# TUSB8041_Connectors_2.net
KiCad netlist of a schematic drawn in Altium Designer
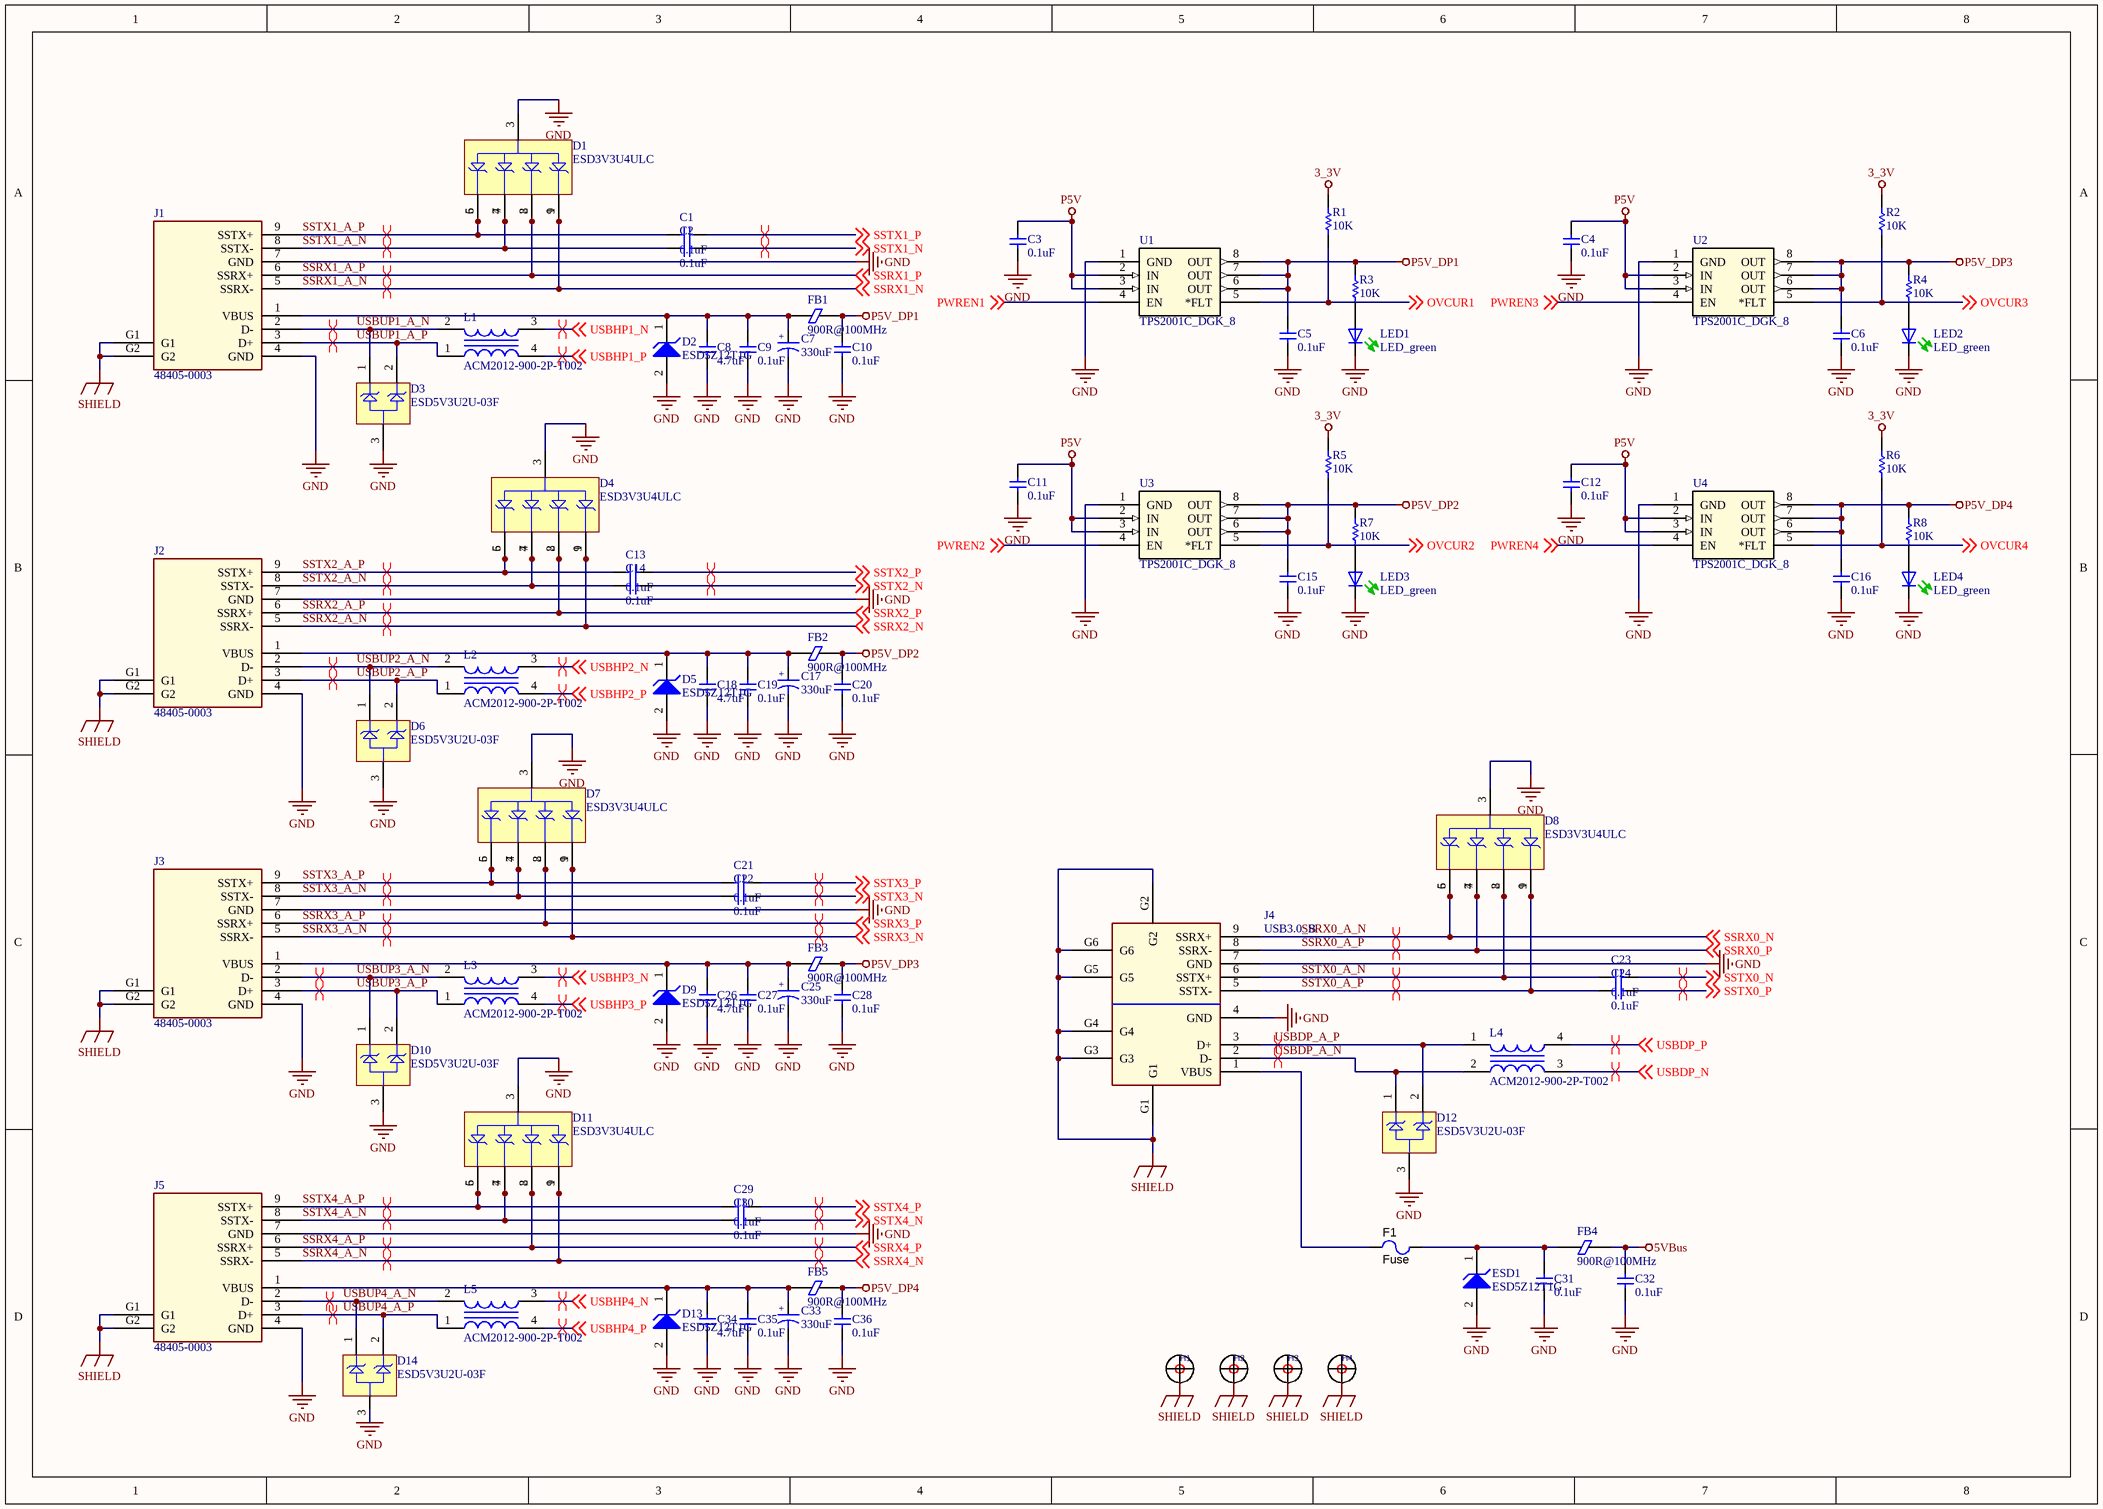
[diagram p0: TUSB8041_Connectors_2.SchDoc]

(export (version "E")
  (design (tool "Eeschema 10.0.6"))
  (components
    (comp (ref "C1")
      (value "0.1uF")
      (footprint "CAP0402")
      (description "Capacitor")
      (fields (field (name "PUBLISHER") "Altium Limited"))
      (libsource (lib "TUSB8041_USB_3.0_Hub") (part "CAP"))
    )
    (comp (ref "C2")
      (value "0.1uF")
      (footprint "CAP0402")
      (description "Capacitor")
      (fields (field (name "PUBLISHER") "Altium Limited"))
      (libsource (lib "TUSB8041_USB_3.0_Hub") (part "CAP"))
    )
    (comp (ref "C3")
      (value "0.1uF")
      (footprint "CAP0603")
      (description "Capacitor")
      (fields (field (name "PUBLISHER") "Altium Limited"))
      (libsource (lib "TUSB8041_USB_3.0_Hub") (part "CAP"))
    )
    (comp (ref "C4")
      (value "0.1uF")
      (footprint "CAP0603")
      (description "Capacitor")
      (fields (field (name "PUBLISHER") "Altium Limited"))
      (libsource (lib "TUSB8041_USB_3.0_Hub") (part "CAP"))
    )
    (comp (ref "C5")
      (value "0.1uF")
      (footprint "CAP0603")
      (description "Capacitor")
      (fields (field (name "PUBLISHER") "Altium Limited"))
      (libsource (lib "TUSB8041_USB_3.0_Hub") (part "CAP"))
    )
    (comp (ref "C6")
      (value "0.1uF")
      (footprint "CAP0603")
      (description "Capacitor")
      (fields (field (name "PUBLISHER") "Altium Limited"))
      (libsource (lib "TUSB8041_USB_3.0_Hub") (part "CAP"))
    )
    (comp (ref "C7")
      (value "330uF")
      (footprint "CAP7343_TANT")
      (libsource (lib "TUSB8041_USB_3.0_Hub") (part "CAP_POL"))
    )
    (comp (ref "C8")
      (value "4.7uF")
      (footprint "CAP0603")
      (description "Capacitor")
      (fields (field (name "PUBLISHER") "Altium Limited"))
      (libsource (lib "TUSB8041_USB_3.0_Hub") (part "CAP"))
    )
    (comp (ref "C9")
      (value "0.1uF")
      (footprint "CAP0603")
      (description "Capacitor")
      (fields (field (name "PUBLISHER") "Altium Limited"))
      (libsource (lib "TUSB8041_USB_3.0_Hub") (part "CAP"))
    )
    (comp (ref "C10")
      (value "0.1uF")
      (footprint "CAP0603")
      (description "Capacitor")
      (fields (field (name "PUBLISHER") "Altium Limited"))
      (libsource (lib "TUSB8041_USB_3.0_Hub") (part "CAP"))
    )
    (comp (ref "C11")
      (value "0.1uF")
      (footprint "CAP0603")
      (description "Capacitor")
      (fields (field (name "PUBLISHER") "Altium Limited"))
      (libsource (lib "TUSB8041_USB_3.0_Hub") (part "CAP"))
    )
    (comp (ref "C12")
      (value "0.1uF")
      (footprint "CAP0603")
      (description "Capacitor")
      (fields (field (name "PUBLISHER") "Altium Limited"))
      (libsource (lib "TUSB8041_USB_3.0_Hub") (part "CAP"))
    )
    (comp (ref "C13")
      (value "0.1uF")
      (footprint "CAP0402")
      (description "Capacitor")
      (fields (field (name "PUBLISHER") "Altium Limited"))
      (libsource (lib "TUSB8041_USB_3.0_Hub") (part "CAP"))
    )
    (comp (ref "C14")
      (value "0.1uF")
      (footprint "CAP0402")
      (description "Capacitor")
      (fields (field (name "PUBLISHER") "Altium Limited"))
      (libsource (lib "TUSB8041_USB_3.0_Hub") (part "CAP"))
    )
    (comp (ref "C15")
      (value "0.1uF")
      (footprint "CAP0603")
      (description "Capacitor")
      (fields (field (name "PUBLISHER") "Altium Limited"))
      (libsource (lib "TUSB8041_USB_3.0_Hub") (part "CAP"))
    )
    (comp (ref "C16")
      (value "0.1uF")
      (footprint "CAP0603")
      (description "Capacitor")
      (fields (field (name "PUBLISHER") "Altium Limited"))
      (libsource (lib "TUSB8041_USB_3.0_Hub") (part "CAP"))
    )
    (comp (ref "C17")
      (value "330uF")
      (footprint "CAP7343_TANT")
      (libsource (lib "TUSB8041_USB_3.0_Hub") (part "CAP_POL"))
    )
    (comp (ref "C18")
      (value "4.7uF")
      (footprint "CAP0603")
      (description "Capacitor")
      (fields (field (name "PUBLISHER") "Altium Limited"))
      (libsource (lib "TUSB8041_USB_3.0_Hub") (part "CAP"))
    )
    (comp (ref "C19")
      (value "0.1uF")
      (footprint "CAP0603")
      (description "Capacitor")
      (fields (field (name "PUBLISHER") "Altium Limited"))
      (libsource (lib "TUSB8041_USB_3.0_Hub") (part "CAP"))
    )
    (comp (ref "C20")
      (value "0.1uF")
      (footprint "CAP0603")
      (description "Capacitor")
      (fields (field (name "PUBLISHER") "Altium Limited"))
      (libsource (lib "TUSB8041_USB_3.0_Hub") (part "CAP"))
    )
    (comp (ref "C21")
      (value "0.1uF")
      (footprint "CAP0402")
      (description "Capacitor")
      (fields (field (name "PUBLISHER") "Altium Limited"))
      (libsource (lib "TUSB8041_USB_3.0_Hub") (part "CAP"))
    )
    (comp (ref "C22")
      (value "0.1uF")
      (footprint "CAP0402")
      (description "Capacitor")
      (fields (field (name "PUBLISHER") "Altium Limited"))
      (libsource (lib "TUSB8041_USB_3.0_Hub") (part "CAP"))
    )
    (comp (ref "C23")
      (value "0.1uF")
      (footprint "CAP0402")
      (description "Capacitor")
      (fields (field (name "PUBLISHER") "Altium Limited"))
      (libsource (lib "TUSB8041_USB_3.0_Hub") (part "CAP"))
    )
    (comp (ref "C24")
      (value "0.1uF")
      (footprint "CAP0402")
      (description "Capacitor")
      (fields (field (name "PUBLISHER") "Altium Limited"))
      (libsource (lib "TUSB8041_USB_3.0_Hub") (part "CAP"))
    )
    (comp (ref "C25")
      (value "330uF")
      (footprint "CAP7343_TANT")
      (libsource (lib "TUSB8041_USB_3.0_Hub") (part "CAP_POL"))
    )
    (comp (ref "C26")
      (value "4.7uF")
      (footprint "CAP0603")
      (description "Capacitor")
      (fields (field (name "PUBLISHER") "Altium Limited"))
      (libsource (lib "TUSB8041_USB_3.0_Hub") (part "CAP"))
    )
    (comp (ref "C27")
      (value "0.1uF")
      (footprint "CAP0603")
      (description "Capacitor")
      (fields (field (name "PUBLISHER") "Altium Limited"))
      (libsource (lib "TUSB8041_USB_3.0_Hub") (part "CAP"))
    )
    (comp (ref "C28")
      (value "0.1uF")
      (footprint "CAP0603")
      (description "Capacitor")
      (fields (field (name "PUBLISHER") "Altium Limited"))
      (libsource (lib "TUSB8041_USB_3.0_Hub") (part "CAP"))
    )
    (comp (ref "C29")
      (value "0.1uF")
      (footprint "CAP0402")
      (description "Capacitor")
      (fields (field (name "PUBLISHER") "Altium Limited"))
      (libsource (lib "TUSB8041_USB_3.0_Hub") (part "CAP"))
    )
    (comp (ref "C30")
      (value "0.1uF")
      (footprint "CAP0402")
      (description "Capacitor")
      (fields (field (name "PUBLISHER") "Altium Limited"))
      (libsource (lib "TUSB8041_USB_3.0_Hub") (part "CAP"))
    )
    (comp (ref "C31")
      (value "0.1uF")
      (footprint "CAP0603")
      (description "Capacitor")
      (fields (field (name "PUBLISHER") "Altium Limited"))
      (libsource (lib "TUSB8041_USB_3.0_Hub") (part "CAP"))
    )
    (comp (ref "C32")
      (value "0.1uF")
      (footprint "CAP0603")
      (description "Capacitor")
      (fields (field (name "PUBLISHER") "Altium Limited"))
      (libsource (lib "TUSB8041_USB_3.0_Hub") (part "CAP"))
    )
    (comp (ref "C33")
      (value "330uF")
      (footprint "CAP7343_TANT")
      (libsource (lib "TUSB8041_USB_3.0_Hub") (part "CAP_POL"))
    )
    (comp (ref "C34")
      (value "4.7uF")
      (footprint "CAP0603")
      (description "Capacitor")
      (fields (field (name "PUBLISHER") "Altium Limited"))
      (libsource (lib "TUSB8041_USB_3.0_Hub") (part "CAP"))
    )
    (comp (ref "C35")
      (value "0.1uF")
      (footprint "CAP0603")
      (description "Capacitor")
      (fields (field (name "PUBLISHER") "Altium Limited"))
      (libsource (lib "TUSB8041_USB_3.0_Hub") (part "CAP"))
    )
    (comp (ref "C36")
      (value "0.1uF")
      (footprint "CAP0603")
      (description "Capacitor")
      (fields (field (name "PUBLISHER") "Altium Limited"))
      (libsource (lib "TUSB8041_USB_3.0_Hub") (part "CAP"))
    )
    (comp (ref "D1")
      (value "ESD3V3U4ULC")
      (footprint "PG-TSLP-9-1")
      (description "Ultra-Low Capacitance ESD / Transient Protection Array, -40 to 125 degC, PG-TSLP-9-1, Reel, Green")
      (fields (field (name "MANUFACTURER") "Infineon"))
      (libsource (lib "小车") (part "ESD3V3U4ULC"))
    )
    (comp (ref "D2")
      (value "ESD5Z12T1G")
      (footprint "ONSC-SOD-523-2-502-01_V")
      (fields (field (name "MANUFACTURER") "On Semiconductor"))
      (libsource (lib "Altium Content Vault") (part "ONSC-K1A2-2"))
    )
    (comp (ref "D3")
      (value "ESD5V3U2U-03F")
      (footprint "INF-PG-TSFP-3-1_V")
      (description "Ultra-Low Capacitance ESD Diode Array, -40 to 125 degC, PG-TSFP-3-1, Reel, Green")
      (fields (field (name "MANUFACTURER") "Infineon"))
      (libsource (lib "Altium Content Vault") (part "INF-D_K1K2A3-3-A"))
    )
    (comp (ref "D4")
      (value "ESD3V3U4ULC")
      (footprint "PG-TSLP-9-1")
      (description "Ultra-Low Capacitance ESD / Transient Protection Array, -40 to 125 degC, PG-TSLP-9-1, Reel, Green")
      (fields (field (name "MANUFACTURER") "Infineon"))
      (libsource (lib "小车") (part "ESD3V3U4ULC"))
    )
    (comp (ref "D5")
      (value "ESD5Z12T1G")
      (footprint "ONSC-SOD-523-2-502-01_V")
      (fields (field (name "MANUFACTURER") "On Semiconductor"))
      (libsource (lib "Altium Content Vault") (part "ONSC-K1A2-2"))
    )
    (comp (ref "D6")
      (value "ESD5V3U2U-03F")
      (footprint "INF-PG-TSFP-3-1_V")
      (description "Ultra-Low Capacitance ESD Diode Array, -40 to 125 degC, PG-TSFP-3-1, Reel, Green")
      (fields (field (name "MANUFACTURER") "Infineon"))
      (libsource (lib "Altium Content Vault") (part "INF-D_K1K2A3-3-A"))
    )
    (comp (ref "D7")
      (value "ESD3V3U4ULC")
      (footprint "PG-TSLP-9-1")
      (description "Ultra-Low Capacitance ESD / Transient Protection Array, -40 to 125 degC, PG-TSLP-9-1, Reel, Green")
      (fields (field (name "MANUFACTURER") "Infineon"))
      (libsource (lib "小车") (part "ESD3V3U4ULC"))
    )
    (comp (ref "D8")
      (value "ESD3V3U4ULC")
      (footprint "PG-TSLP-9-1")
      (description "Ultra-Low Capacitance ESD / Transient Protection Array, -40 to 125 degC, PG-TSLP-9-1, Reel, Green")
      (fields (field (name "MANUFACTURER") "Infineon"))
      (libsource (lib "小车") (part "ESD3V3U4ULC"))
    )
    (comp (ref "D9")
      (value "ESD5Z12T1G")
      (footprint "ONSC-SOD-523-2-502-01_V")
      (fields (field (name "MANUFACTURER") "On Semiconductor"))
      (libsource (lib "Altium Content Vault") (part "ONSC-K1A2-2"))
    )
    (comp (ref "D10")
      (value "ESD5V3U2U-03F")
      (footprint "INF-PG-TSFP-3-1_V")
      (description "Ultra-Low Capacitance ESD Diode Array, -40 to 125 degC, PG-TSFP-3-1, Reel, Green")
      (fields (field (name "MANUFACTURER") "Infineon"))
      (libsource (lib "Altium Content Vault") (part "INF-D_K1K2A3-3-A"))
    )
    (comp (ref "D11")
      (value "ESD3V3U4ULC")
      (footprint "PG-TSLP-9-1")
      (description "Ultra-Low Capacitance ESD / Transient Protection Array, -40 to 125 degC, PG-TSLP-9-1, Reel, Green")
      (fields (field (name "MANUFACTURER") "Infineon"))
      (libsource (lib "小车") (part "ESD3V3U4ULC"))
    )
    (comp (ref "D12")
      (value "ESD5V3U2U-03F")
      (footprint "INF-PG-TSFP-3-1_V")
      (description "Ultra-Low Capacitance ESD Diode Array, -40 to 125 degC, PG-TSFP-3-1, Reel, Green")
      (fields (field (name "MANUFACTURER") "Infineon"))
      (libsource (lib "Altium Content Vault") (part "INF-D_K1K2A3-3-A"))
    )
    (comp (ref "D13")
      (value "ESD5Z12T1G")
      (footprint "ONSC-SOD-523-2-502-01_V")
      (fields (field (name "MANUFACTURER") "On Semiconductor"))
      (libsource (lib "Altium Content Vault") (part "ONSC-K1A2-2"))
    )
    (comp (ref "D14")
      (value "ESD5V3U2U-03F")
      (footprint "INF-PG-TSFP-3-1_V")
      (description "Ultra-Low Capacitance ESD Diode Array, -40 to 125 degC, PG-TSFP-3-1, Reel, Green")
      (fields (field (name "MANUFACTURER") "Infineon"))
      (libsource (lib "Altium Content Vault") (part "INF-D_K1K2A3-3-A"))
    )
    (comp (ref "ESD1")
      (value "ESD5Z12T1G")
      (footprint "ONSC-SOD-523-2-502-01_V")
      (fields (field (name "MANUFACTURER") "On Semiconductor"))
      (libsource (lib "Altium Content Vault") (part "ONSC-K1A2-2"))
    )
    (comp (ref "F1")
      (value "Fuse")
      (footprint "FUSE1206")
      (fields
        (field (name "PARTNUMBER") "NANOSMDC020F-2")
        (field (name "MANUFACTURER") "TE Connectivity")
        (field (name "PUBLISHER") "Texas Instruments")
        (field (name "SYMBOLCREATOR") "a0412235")
      )
      (libsource (lib "TUSB8041_USB_3.0_Hub") (part "Fuse"))
    )
    (comp (ref "FB1")
      (value "900R@100MHz")
      (footprint "L0805")
      (libsource (lib "TUSB8041_USB_3.0_Hub") (part "Ferrite Bead"))
    )
    (comp (ref "FB2")
      (value "900R@100MHz")
      (footprint "L0805")
      (libsource (lib "TUSB8041_USB_3.0_Hub") (part "Ferrite Bead"))
    )
    (comp (ref "FB3")
      (value "900R@100MHz")
      (footprint "L0805")
      (libsource (lib "TUSB8041_USB_3.0_Hub") (part "Ferrite Bead"))
    )
    (comp (ref "FB4")
      (value "900R@100MHz")
      (footprint "L0805")
      (libsource (lib "TUSB8041_USB_3.0_Hub") (part "Ferrite Bead"))
    )
    (comp (ref "FB5")
      (value "900R@100MHz")
      (footprint "L0805")
      (libsource (lib "TUSB8041_USB_3.0_Hub") (part "Ferrite Bead"))
    )
    (comp (ref "H1")
      (value "HOLE")
      (footprint "HOLE_Φ3_1_2D")
      (libsource (lib "TUSB8041_USB_3.0_Hub") (part "HOLE"))
    )
    (comp (ref "H2")
      (value "HOLE")
      (footprint "HOLE_Φ3_1_2D")
      (libsource (lib "TUSB8041_USB_3.0_Hub") (part "HOLE"))
    )
    (comp (ref "H3")
      (value "HOLE")
      (footprint "HOLE_Φ3_1_2D")
      (libsource (lib "TUSB8041_USB_3.0_Hub") (part "HOLE"))
    )
    (comp (ref "H4")
      (value "HOLE")
      (footprint "HOLE_Φ3_1_2D")
      (libsource (lib "TUSB8041_USB_3.0_Hub") (part "HOLE"))
    )
    (comp (ref "J1")
      (value "48405-0003")
      (footprint "CN_USB30_A")
      (libsource (lib "TUSB8041_USB_3.0_Hub") (part "USB-UEA11123-4HK1-4H"))
    )
    (comp (ref "J2")
      (value "48405-0003")
      (footprint "CN_USB30_A")
      (libsource (lib "TUSB8041_USB_3.0_Hub") (part "USB-UEA11123-4HK1-4H"))
    )
    (comp (ref "J3")
      (value "48405-0003")
      (footprint "CN_USB30_A")
      (libsource (lib "TUSB8041_USB_3.0_Hub") (part "USB-UEA11123-4HK1-4H"))
    )
    (comp (ref "J4")
      (value "USB3.0_B")
      (footprint "ASS_4224_CO")
      (libsource (lib "TUSB8041_USB_3.0_Hub") (part "USB3.0_B"))
    )
    (comp (ref "J5")
      (value "48405-0003")
      (footprint "CN_USB30_A")
      (libsource (lib "TUSB8041_USB_3.0_Hub") (part "USB-UEA11123-4HK1-4H"))
    )
    (comp (ref "L1")
      (value "ACM2012-900-2P-T002")
      (footprint "TDK-ACM2012_V")
      (description "Common Mode Filter, 90 Ohm, 50 V, -40 to 85 degC, 4-Pin SMD, RoHS, Tape and Reel")
      (fields (field (name "PART NO") "ACM2012-900-2P-T") (field (name "MANUFACTURER") "TDKCorporation"))
      (libsource (lib "") (part "IND-CHOKE-4_C_1"))
    )
    (comp (ref "L2")
      (value "ACM2012-900-2P-T002")
      (footprint "TDK-ACM2012_V")
      (description "Common Mode Filter, 90 Ohm, 50 V, -40 to 85 degC, 4-Pin SMD, RoHS, Tape and Reel")
      (fields (field (name "PART NO") "ACM2012-900-2P-T") (field (name "MANUFACTURER") "TDKCorporation"))
      (libsource (lib "") (part "IND-CHOKE-4_C_1"))
    )
    (comp (ref "L3")
      (value "ACM2012-900-2P-T002")
      (footprint "TDK-ACM2012_V")
      (description "Common Mode Filter, 90 Ohm, 50 V, -40 to 85 degC, 4-Pin SMD, RoHS, Tape and Reel")
      (fields (field (name "PART NO") "ACM2012-900-2P-T") (field (name "MANUFACTURER") "TDKCorporation"))
      (libsource (lib "") (part "IND-CHOKE-4_C_1"))
    )
    (comp (ref "L4")
      (value "ACM2012-900-2P-T002")
      (footprint "TDK-ACM2012_V")
      (description "Common Mode Filter, 90 Ohm, 50 V, -40 to 85 degC, 4-Pin SMD, RoHS, Tape and Reel")
      (fields (field (name "PART NO") "ACM2012-900-2P-T") (field (name "MANUFACTURER") "TDKCorporation"))
      (libsource (lib "Altium Content Vault") (part "IND-CHOKE-4_C"))
    )
    (comp (ref "L5")
      (value "ACM2012-900-2P-T002")
      (footprint "TDK-ACM2012_V")
      (description "Common Mode Filter, 90 Ohm, 50 V, -40 to 85 degC, 4-Pin SMD, RoHS, Tape and Reel")
      (fields (field (name "PART NO") "ACM2012-900-2P-T") (field (name "MANUFACTURER") "TDKCorporation"))
      (libsource (lib "") (part "IND-CHOKE-4_C_1"))
    )
    (comp (ref "LED1")
      (value "LED_green")
      (footprint "LED-0603-GREEN")
      (libsource (lib "TUSB8041_USB_3.0_Hub") (part "LED_green"))
    )
    (comp (ref "LED2")
      (value "LED_green")
      (footprint "LED-0603-GREEN")
      (libsource (lib "TUSB8041_USB_3.0_Hub") (part "LED_green"))
    )
    (comp (ref "LED3")
      (value "LED_green")
      (footprint "LED-0603-GREEN")
      (libsource (lib "TUSB8041_USB_3.0_Hub") (part "LED_green"))
    )
    (comp (ref "LED4")
      (value "LED_green")
      (footprint "LED-0603-GREEN")
      (libsource (lib "TUSB8041_USB_3.0_Hub") (part "LED_green"))
    )
    (comp (ref "R1")
      (value "10K")
      (footprint "RES0603")
      (description "Resistor")
      (fields (field (name "PUBLISHER") "Altium Limited"))
      (libsource (lib "TUSB8041_USB_3.0_Hub") (part "RES"))
    )
    (comp (ref "R2")
      (value "10K")
      (footprint "RES0603")
      (description "Resistor")
      (fields (field (name "PUBLISHER") "Altium Limited"))
      (libsource (lib "TUSB8041_USB_3.0_Hub") (part "RES"))
    )
    (comp (ref "R3")
      (value "10K")
      (footprint "RES0603")
      (description "Resistor")
      (fields (field (name "PUBLISHER") "Altium Limited"))
      (libsource (lib "TUSB8041_USB_3.0_Hub") (part "RES"))
    )
    (comp (ref "R4")
      (value "10K")
      (footprint "RES0603")
      (description "Resistor")
      (fields (field (name "PUBLISHER") "Altium Limited"))
      (libsource (lib "TUSB8041_USB_3.0_Hub") (part "RES"))
    )
    (comp (ref "R5")
      (value "10K")
      (footprint "RES0603")
      (description "Resistor")
      (fields (field (name "PUBLISHER") "Altium Limited"))
      (libsource (lib "TUSB8041_USB_3.0_Hub") (part "RES"))
    )
    (comp (ref "R6")
      (value "10K")
      (footprint "RES0603")
      (description "Resistor")
      (fields (field (name "PUBLISHER") "Altium Limited"))
      (libsource (lib "TUSB8041_USB_3.0_Hub") (part "RES"))
    )
    (comp (ref "R7")
      (value "10K")
      (footprint "RES0603")
      (description "Resistor")
      (fields (field (name "PUBLISHER") "Altium Limited"))
      (libsource (lib "TUSB8041_USB_3.0_Hub") (part "RES"))
    )
    (comp (ref "R8")
      (value "10K")
      (footprint "RES0603")
      (description "Resistor")
      (fields (field (name "PUBLISHER") "Altium Limited"))
      (libsource (lib "TUSB8041_USB_3.0_Hub") (part "RES"))
    )
    (comp (ref "U1")
      (value "TPS2001C_DGK_8")
      (footprint "VSSOP8")
      (description "2A_MOS_PSW")
      (fields
        (field (name "MANUFACTURER_PART_NUMBER") "tps2001c_dgk_8")
        (field (name "GENERIC_PART_NUMBER") "TPS2001C")
      )
      (libsource (lib "TUSB8041_USB_3.0_Hub") (part "TPS2001C_DGK_8"))
    )
    (comp (ref "U2")
      (value "TPS2001C_DGK_8")
      (footprint "VSSOP8")
      (description "2A_MOS_PSW")
      (fields
        (field (name "MANUFACTURER_PART_NUMBER") "tps2001c_dgk_8")
        (field (name "GENERIC_PART_NUMBER") "TPS2001C")
      )
      (libsource (lib "TUSB8041_USB_3.0_Hub") (part "TPS2001C_DGK_8"))
    )
    (comp (ref "U3")
      (value "TPS2001C_DGK_8")
      (footprint "VSSOP8")
      (description "2A_MOS_PSW")
      (fields
        (field (name "MANUFACTURER_PART_NUMBER") "tps2001c_dgk_8")
        (field (name "GENERIC_PART_NUMBER") "TPS2001C")
      )
      (libsource (lib "TUSB8041_USB_3.0_Hub") (part "TPS2001C_DGK_8"))
    )
    (comp (ref "U4")
      (value "TPS2001C_DGK_8")
      (footprint "VSSOP8")
      (description "2A_MOS_PSW")
      (fields
        (field (name "MANUFACTURER_PART_NUMBER") "tps2001c_dgk_8")
        (field (name "GENERIC_PART_NUMBER") "TPS2001C")
      )
      (libsource (lib "TUSB8041_USB_3.0_Hub") (part "TPS2001C_DGK_8"))
    )
  )
  (nets
    (net (code "1") (name "/SSTX0_A_N") (class "Default")
      (node (ref "C23") (pin "2") (pinfunction "2_2") (pintype "passive"))
      (node (ref "D8") (pin "2") (pinfunction "K2_2") (pintype "passive"))
      (node (ref "D8") (pin "8") (pinfunction "K8_8") (pintype "passive"))
      (node (ref "J4") (pin "6") (pinfunction "SSTX+_6") (pintype "passive"))
    )
    (net (code "2") (name "/SSTX0_A_P") (class "Default")
      (node (ref "C24") (pin "2") (pinfunction "2_2") (pintype "passive"))
      (node (ref "D8") (pin "1") (pinfunction "K1_1") (pintype "passive"))
      (node (ref "D8") (pin "9") (pinfunction "K9_9") (pintype "passive"))
      (node (ref "J4") (pin "5") (pinfunction "SSTX-_5") (pintype "passive"))
    )
    (net (code "3") (name "/SSTX1_A_N") (class "Default")
      (node (ref "C2") (pin "2") (pinfunction "2_2") (pintype "passive"))
      (node (ref "D1") (pin "4") (pinfunction "K4_4") (pintype "passive"))
      (node (ref "D1") (pin "7") (pinfunction "K7_7") (pintype "passive"))
      (node (ref "J1") (pin "8") (pinfunction "SSTX-_8") (pintype "passive"))
    )
    (net (code "4") (name "/SSTX1_A_P") (class "Default")
      (node (ref "C1") (pin "2") (pinfunction "2_2") (pintype "passive"))
      (node (ref "D1") (pin "5") (pinfunction "K5_5") (pintype "passive"))
      (node (ref "D1") (pin "6") (pinfunction "K6_6") (pintype "passive"))
      (node (ref "J1") (pin "9") (pinfunction "SSTX+_9") (pintype "passive"))
    )
    (net (code "5") (name "/SSTX2_A_N") (class "Default")
      (node (ref "C14") (pin "2") (pinfunction "2_2") (pintype "passive"))
      (node (ref "D4") (pin "4") (pinfunction "K4_4") (pintype "passive"))
      (node (ref "D4") (pin "7") (pinfunction "K7_7") (pintype "passive"))
      (node (ref "J2") (pin "8") (pinfunction "SSTX-_8") (pintype "passive"))
    )
    (net (code "6") (name "/SSTX2_A_P") (class "Default")
      (node (ref "C13") (pin "2") (pinfunction "2_2") (pintype "passive"))
      (node (ref "D4") (pin "5") (pinfunction "K5_5") (pintype "passive"))
      (node (ref "D4") (pin "6") (pinfunction "K6_6") (pintype "passive"))
      (node (ref "J2") (pin "9") (pinfunction "SSTX+_9") (pintype "passive"))
    )
    (net (code "7") (name "/SSTX3_A_N") (class "Default")
      (node (ref "C22") (pin "2") (pinfunction "2_2") (pintype "passive"))
      (node (ref "D7") (pin "4") (pinfunction "K4_4") (pintype "passive"))
      (node (ref "D7") (pin "7") (pinfunction "K7_7") (pintype "passive"))
      (node (ref "J3") (pin "8") (pinfunction "SSTX-_8") (pintype "passive"))
    )
    (net (code "8") (name "/SSTX3_A_P") (class "Default")
      (node (ref "C21") (pin "2") (pinfunction "2_2") (pintype "passive"))
      (node (ref "D7") (pin "5") (pinfunction "K5_5") (pintype "passive"))
      (node (ref "D7") (pin "6") (pinfunction "K6_6") (pintype "passive"))
      (node (ref "J3") (pin "9") (pinfunction "SSTX+_9") (pintype "passive"))
    )
    (net (code "9") (name "/SSTX4_A_N") (class "Default")
      (node (ref "C30") (pin "2") (pinfunction "2_2") (pintype "passive"))
      (node (ref "D11") (pin "4") (pinfunction "K4_4") (pintype "passive"))
      (node (ref "D11") (pin "7") (pinfunction "K7_7") (pintype "passive"))
      (node (ref "J5") (pin "8") (pinfunction "SSTX-_8") (pintype "passive"))
    )
    (net (code "10") (name "/SSTX4_A_P") (class "Default")
      (node (ref "C29") (pin "2") (pinfunction "2_2") (pintype "passive"))
      (node (ref "D11") (pin "5") (pinfunction "K5_5") (pintype "passive"))
      (node (ref "D11") (pin "6") (pinfunction "K6_6") (pintype "passive"))
      (node (ref "J5") (pin "9") (pinfunction "SSTX+_9") (pintype "passive"))
    )
    (net (code "11") (name "/USBDP_A_N") (class "Default")
      (node (ref "D12") (pin "1") (pinfunction "K1_1") (pintype "passive"))
      (node (ref "J4") (pin "2") (pinfunction "D-_2") (pintype "passive"))
      (node (ref "L4") (pin "2") (pinfunction "2_2") (pintype "passive"))
    )
    (net (code "12") (name "/USBDP_A_P") (class "Default")
      (node (ref "D12") (pin "2") (pinfunction "K2_2") (pintype "passive"))
      (node (ref "J4") (pin "3") (pinfunction "D+_3") (pintype "passive"))
      (node (ref "L4") (pin "1") (pinfunction "1_1") (pintype "passive"))
    )
    (net (code "13") (name "/USBUP1_A_N") (class "Default")
      (node (ref "D3") (pin "1") (pinfunction "K1_1") (pintype "passive"))
      (node (ref "J1") (pin "2") (pinfunction "D-_2") (pintype "passive"))
      (node (ref "L1") (pin "2") (pinfunction "2_2") (pintype "passive"))
    )
    (net (code "14") (name "/USBUP1_A_P") (class "Default")
      (node (ref "D3") (pin "2") (pinfunction "K2_2") (pintype "passive"))
      (node (ref "J1") (pin "3") (pinfunction "D+_3") (pintype "passive"))
      (node (ref "L1") (pin "1") (pinfunction "1_1") (pintype "passive"))
    )
    (net (code "15") (name "/USBUP2_A_N") (class "Default")
      (node (ref "D6") (pin "1") (pinfunction "K1_1") (pintype "passive"))
      (node (ref "J2") (pin "2") (pinfunction "D-_2") (pintype "passive"))
      (node (ref "L2") (pin "2") (pinfunction "2_2") (pintype "passive"))
    )
    (net (code "16") (name "/USBUP2_A_P") (class "Default")
      (node (ref "D6") (pin "2") (pinfunction "K2_2") (pintype "passive"))
      (node (ref "J2") (pin "3") (pinfunction "D+_3") (pintype "passive"))
      (node (ref "L2") (pin "1") (pinfunction "1_1") (pintype "passive"))
    )
    (net (code "17") (name "/USBUP3_A_N") (class "Default")
      (node (ref "D10") (pin "1") (pinfunction "K1_1") (pintype "passive"))
      (node (ref "J3") (pin "2") (pinfunction "D-_2") (pintype "passive"))
      (node (ref "L3") (pin "2") (pinfunction "2_2") (pintype "passive"))
    )
    (net (code "18") (name "/USBUP3_A_P") (class "Default")
      (node (ref "D10") (pin "2") (pinfunction "K2_2") (pintype "passive"))
      (node (ref "J3") (pin "3") (pinfunction "D+_3") (pintype "passive"))
      (node (ref "L3") (pin "1") (pinfunction "1_1") (pintype "passive"))
    )
    (net (code "19") (name "/USBUP4_A_N") (class "Default")
      (node (ref "D14") (pin "1") (pinfunction "K1_1") (pintype "passive"))
      (node (ref "J5") (pin "2") (pinfunction "D-_2") (pintype "passive"))
      (node (ref "L5") (pin "2") (pinfunction "2_2") (pintype "passive"))
    )
    (net (code "20") (name "/USBUP4_A_P") (class "Default")
      (node (ref "D14") (pin "2") (pinfunction "K2_2") (pintype "passive"))
      (node (ref "J5") (pin "3") (pinfunction "D+_3") (pintype "passive"))
      (node (ref "L5") (pin "1") (pinfunction "1_1") (pintype "passive"))
    )
    (net (code "21") (name "3_3V") (class "Default")
      (node (ref "R1") (pin "1") (pinfunction "1_1") (pintype "passive"))
      (node (ref "R2") (pin "1") (pinfunction "1_1") (pintype "passive"))
      (node (ref "R5") (pin "1") (pinfunction "1_1") (pintype "passive"))
      (node (ref "R6") (pin "1") (pinfunction "1_1") (pintype "passive"))
    )
    (net (code "22") (name "5VBus") (class "Default")
      (node (ref "C32") (pin "2") (pinfunction "2_2") (pintype "passive"))
      (node (ref "FB4") (pin "2") (pintype "passive"))
    )
    (net (code "23") (name "GND") (class "Default")
      (node (ref "C10") (pin "1") (pinfunction "1_1") (pintype "passive"))
      (node (ref "C11") (pin "1") (pinfunction "1_1") (pintype "passive"))
      (node (ref "C12") (pin "1") (pinfunction "1_1") (pintype "passive"))
      (node (ref "C15") (pin "1") (pinfunction "1_1") (pintype "passive"))
      (node (ref "C16") (pin "1") (pinfunction "1_1") (pintype "passive"))
      (node (ref "C17") (pin "2") (pinfunction "2_2") (pintype "passive"))
      (node (ref "C18") (pin "1") (pinfunction "1_1") (pintype "passive"))
      (node (ref "C19") (pin "1") (pinfunction "1_1") (pintype "passive"))
      (node (ref "C20") (pin "1") (pinfunction "1_1") (pintype "passive"))
      (node (ref "C25") (pin "2") (pinfunction "2_2") (pintype "passive"))
      (node (ref "C26") (pin "1") (pinfunction "1_1") (pintype "passive"))
      (node (ref "C27") (pin "1") (pinfunction "1_1") (pintype "passive"))
      (node (ref "C28") (pin "1") (pinfunction "1_1") (pintype "passive"))
      (node (ref "C3") (pin "1") (pinfunction "1_1") (pintype "passive"))
      (node (ref "C31") (pin "1") (pinfunction "1_1") (pintype "passive"))
      (node (ref "C32") (pin "1") (pinfunction "1_1") (pintype "passive"))
      (node (ref "C33") (pin "2") (pinfunction "2_2") (pintype "passive"))
      (node (ref "C34") (pin "1") (pinfunction "1_1") (pintype "passive"))
      (node (ref "C35") (pin "1") (pinfunction "1_1") (pintype "passive"))
      (node (ref "C36") (pin "1") (pinfunction "1_1") (pintype "passive"))
      (node (ref "C4") (pin "1") (pinfunction "1_1") (pintype "passive"))
      (node (ref "C5") (pin "1") (pinfunction "1_1") (pintype "passive"))
      (node (ref "C6") (pin "1") (pinfunction "1_1") (pintype "passive"))
      (node (ref "C7") (pin "2") (pinfunction "2_2") (pintype "passive"))
      (node (ref "C8") (pin "1") (pinfunction "1_1") (pintype "passive"))
      (node (ref "C9") (pin "1") (pinfunction "1_1") (pintype "passive"))
      (node (ref "D1") (pin "3") (pinfunction "A_3") (pintype "passive"))
      (node (ref "D10") (pin "3") (pinfunction "A_3") (pintype "passive"))
      (node (ref "D11") (pin "3") (pinfunction "A_3") (pintype "passive"))
      (node (ref "D12") (pin "3") (pinfunction "A_3") (pintype "passive"))
      (node (ref "D13") (pin "2") (pinfunction "A_2") (pintype "passive"))
      (node (ref "D14") (pin "3") (pinfunction "A_3") (pintype "passive"))
      (node (ref "D2") (pin "2") (pinfunction "A_2") (pintype "passive"))
      (node (ref "D3") (pin "3") (pinfunction "A_3") (pintype "passive"))
      (node (ref "D4") (pin "3") (pinfunction "A_3") (pintype "passive"))
      (node (ref "D5") (pin "2") (pinfunction "A_2") (pintype "passive"))
      (node (ref "D6") (pin "3") (pinfunction "A_3") (pintype "passive"))
      (node (ref "D7") (pin "3") (pinfunction "A_3") (pintype "passive"))
      (node (ref "D8") (pin "3") (pinfunction "A_3") (pintype "passive"))
      (node (ref "D9") (pin "2") (pinfunction "A_2") (pintype "passive"))
      (node (ref "ESD1") (pin "2") (pinfunction "A_2") (pintype "passive"))
      (node (ref "J1") (pin "4") (pinfunction "GND_4") (pintype "power_in"))
      (node (ref "J1") (pin "7") (pinfunction "GND_7") (pintype "power_in"))
      (node (ref "J2") (pin "4") (pinfunction "GND_4") (pintype "power_in"))
      (node (ref "J2") (pin "7") (pinfunction "GND_7") (pintype "power_in"))
      (node (ref "J3") (pin "4") (pinfunction "GND_4") (pintype "power_in"))
      (node (ref "J3") (pin "7") (pinfunction "GND_7") (pintype "power_in"))
      (node (ref "J4") (pin "4") (pinfunction "GND_4") (pintype "power_in"))
      (node (ref "J4") (pin "7") (pinfunction "GND_7") (pintype "power_in"))
      (node (ref "J5") (pin "4") (pinfunction "GND_4") (pintype "power_in"))
      (node (ref "J5") (pin "7") (pinfunction "GND_7") (pintype "power_in"))
      (node (ref "LED1") (pin "K") (pinfunction "C_K") (pintype "power_in"))
      (node (ref "LED2") (pin "K") (pinfunction "C_K") (pintype "power_in"))
      (node (ref "LED3") (pin "K") (pinfunction "C_K") (pintype "power_in"))
      (node (ref "LED4") (pin "K") (pinfunction "C_K") (pintype "power_in"))
      (node (ref "U1") (pin "1") (pinfunction "GND_1") (pintype "power_in"))
      (node (ref "U2") (pin "1") (pinfunction "GND_1") (pintype "power_in"))
      (node (ref "U3") (pin "1") (pinfunction "GND_1") (pintype "power_in"))
      (node (ref "U4") (pin "1") (pinfunction "GND_1") (pintype "power_in"))
    )
    (net (code "24") (name "Net-(D2-K)") (class "Default")
      (node (ref "C7") (pin "1") (pinfunction "1_1") (pintype "passive"))
      (node (ref "C8") (pin "2") (pinfunction "2_2") (pintype "passive"))
      (node (ref "C9") (pin "2") (pinfunction "2_2") (pintype "passive"))
      (node (ref "D2") (pin "1") (pinfunction "K_1") (pintype "passive"))
      (node (ref "FB1") (pin "1") (pintype "passive"))
      (node (ref "J1") (pin "1") (pinfunction "VBUS_1") (pintype "passive"))
    )
    (net (code "25") (name "Net-(D5-K)") (class "Default")
      (node (ref "C17") (pin "1") (pinfunction "1_1") (pintype "passive"))
      (node (ref "C18") (pin "2") (pinfunction "2_2") (pintype "passive"))
      (node (ref "C19") (pin "2") (pinfunction "2_2") (pintype "passive"))
      (node (ref "D5") (pin "1") (pinfunction "K_1") (pintype "passive"))
      (node (ref "FB2") (pin "1") (pintype "passive"))
      (node (ref "J2") (pin "1") (pinfunction "VBUS_1") (pintype "passive"))
    )
    (net (code "26") (name "Net-(D9-K)") (class "Default")
      (node (ref "C25") (pin "1") (pinfunction "1_1") (pintype "passive"))
      (node (ref "C26") (pin "2") (pinfunction "2_2") (pintype "passive"))
      (node (ref "C27") (pin "2") (pinfunction "2_2") (pintype "passive"))
      (node (ref "D9") (pin "1") (pinfunction "K_1") (pintype "passive"))
      (node (ref "FB3") (pin "1") (pintype "passive"))
      (node (ref "J3") (pin "1") (pinfunction "VBUS_1") (pintype "passive"))
    )
    (net (code "27") (name "Net-(D13-K)") (class "Default")
      (node (ref "C33") (pin "1") (pinfunction "1_1") (pintype "passive"))
      (node (ref "C34") (pin "2") (pinfunction "2_2") (pintype "passive"))
      (node (ref "C35") (pin "2") (pinfunction "2_2") (pintype "passive"))
      (node (ref "D13") (pin "1") (pinfunction "K_1") (pintype "passive"))
      (node (ref "FB5") (pin "1") (pintype "passive"))
      (node (ref "J5") (pin "1") (pinfunction "VBUS_1") (pintype "passive"))
    )
    (net (code "28") (name "Net-(ESD1-K)") (class "Default")
      (node (ref "C31") (pin "2") (pinfunction "2_2") (pintype "passive"))
      (node (ref "ESD1") (pin "1") (pinfunction "K_1") (pintype "passive"))
      (node (ref "F1") (pin "1") (pinfunction "1_1") (pintype "passive"))
      (node (ref "FB4") (pin "1") (pintype "passive"))
    )
    (net (code "29") (name "Net-(J4-VBUS)") (class "Default")
      (node (ref "F1") (pin "2") (pinfunction "2_2") (pintype "passive"))
      (node (ref "J4") (pin "1") (pinfunction "VBUS_1") (pintype "passive"))
    )
    (net (code "30") (name "Net-(LED1-PadA)") (class "Default")
      (node (ref "LED1") (pin "A") (pinfunction "A_A") (pintype "power_in"))
      (node (ref "R3") (pin "2") (pinfunction "2_2") (pintype "passive"))
    )
    (net (code "31") (name "Net-(LED2-PadA)") (class "Default")
      (node (ref "LED2") (pin "A") (pinfunction "A_A") (pintype "power_in"))
      (node (ref "R4") (pin "2") (pinfunction "2_2") (pintype "passive"))
    )
    (net (code "32") (name "Net-(LED3-PadA)") (class "Default")
      (node (ref "LED3") (pin "A") (pinfunction "A_A") (pintype "power_in"))
      (node (ref "R7") (pin "2") (pinfunction "2_2") (pintype "passive"))
    )
    (net (code "33") (name "Net-(LED4-PadA)") (class "Default")
      (node (ref "LED4") (pin "A") (pinfunction "A_A") (pintype "power_in"))
      (node (ref "R8") (pin "2") (pinfunction "2_2") (pintype "passive"))
    )
    (net (code "34") (name "OVCUR1") (class "Default")
      (node (ref "R1") (pin "2") (pinfunction "2_2") (pintype "passive"))
      (node (ref "U1") (pin "5") (pinfunction "*FLT_5") (pintype "passive"))
    )
    (net (code "35") (name "OVCUR2") (class "Default")
      (node (ref "R5") (pin "2") (pinfunction "2_2") (pintype "passive"))
      (node (ref "U3") (pin "5") (pinfunction "*FLT_5") (pintype "passive"))
    )
    (net (code "36") (name "OVCUR3") (class "Default")
      (node (ref "R2") (pin "2") (pinfunction "2_2") (pintype "passive"))
      (node (ref "U2") (pin "5") (pinfunction "*FLT_5") (pintype "passive"))
    )
    (net (code "37") (name "OVCUR4") (class "Default")
      (node (ref "R6") (pin "2") (pinfunction "2_2") (pintype "passive"))
      (node (ref "U4") (pin "5") (pinfunction "*FLT_5") (pintype "passive"))
    )
    (net (code "38") (name "P5V") (class "Default")
      (node (ref "C11") (pin "2") (pinfunction "2_2") (pintype "passive"))
      (node (ref "C12") (pin "2") (pinfunction "2_2") (pintype "passive"))
      (node (ref "C3") (pin "2") (pinfunction "2_2") (pintype "passive"))
      (node (ref "C4") (pin "2") (pinfunction "2_2") (pintype "passive"))
      (node (ref "U1") (pin "2") (pinfunction "IN_2") (pintype "input"))
      (node (ref "U1") (pin "3") (pinfunction "IN_3") (pintype "input"))
      (node (ref "U2") (pin "2") (pinfunction "IN_2") (pintype "input"))
      (node (ref "U2") (pin "3") (pinfunction "IN_3") (pintype "input"))
      (node (ref "U3") (pin "2") (pinfunction "IN_2") (pintype "input"))
      (node (ref "U3") (pin "3") (pinfunction "IN_3") (pintype "input"))
      (node (ref "U4") (pin "2") (pinfunction "IN_2") (pintype "input"))
      (node (ref "U4") (pin "3") (pinfunction "IN_3") (pintype "input"))
    )
    (net (code "39") (name "P5V_DP1") (class "Default")
      (node (ref "C10") (pin "2") (pinfunction "2_2") (pintype "passive"))
      (node (ref "C5") (pin "2") (pinfunction "2_2") (pintype "passive"))
      (node (ref "FB1") (pin "2") (pintype "passive"))
      (node (ref "R3") (pin "1") (pinfunction "1_1") (pintype "passive"))
      (node (ref "U1") (pin "6") (pinfunction "OUT_6") (pintype "output"))
      (node (ref "U1") (pin "7") (pinfunction "OUT_7") (pintype "output"))
      (node (ref "U1") (pin "8") (pinfunction "OUT_8") (pintype "output"))
    )
    (net (code "40") (name "P5V_DP2") (class "Default")
      (node (ref "C15") (pin "2") (pinfunction "2_2") (pintype "passive"))
      (node (ref "C20") (pin "2") (pinfunction "2_2") (pintype "passive"))
      (node (ref "FB2") (pin "2") (pintype "passive"))
      (node (ref "R7") (pin "1") (pinfunction "1_1") (pintype "passive"))
      (node (ref "U3") (pin "6") (pinfunction "OUT_6") (pintype "output"))
      (node (ref "U3") (pin "7") (pinfunction "OUT_7") (pintype "output"))
      (node (ref "U3") (pin "8") (pinfunction "OUT_8") (pintype "output"))
    )
    (net (code "41") (name "P5V_DP3") (class "Default")
      (node (ref "C28") (pin "2") (pinfunction "2_2") (pintype "passive"))
      (node (ref "C6") (pin "2") (pinfunction "2_2") (pintype "passive"))
      (node (ref "FB3") (pin "2") (pintype "passive"))
      (node (ref "R4") (pin "1") (pinfunction "1_1") (pintype "passive"))
      (node (ref "U2") (pin "6") (pinfunction "OUT_6") (pintype "output"))
      (node (ref "U2") (pin "7") (pinfunction "OUT_7") (pintype "output"))
      (node (ref "U2") (pin "8") (pinfunction "OUT_8") (pintype "output"))
    )
    (net (code "42") (name "P5V_DP4") (class "Default")
      (node (ref "C16") (pin "2") (pinfunction "2_2") (pintype "passive"))
      (node (ref "C36") (pin "2") (pinfunction "2_2") (pintype "passive"))
      (node (ref "FB5") (pin "2") (pintype "passive"))
      (node (ref "R8") (pin "1") (pinfunction "1_1") (pintype "passive"))
      (node (ref "U4") (pin "6") (pinfunction "OUT_6") (pintype "output"))
      (node (ref "U4") (pin "7") (pinfunction "OUT_7") (pintype "output"))
      (node (ref "U4") (pin "8") (pinfunction "OUT_8") (pintype "output"))
    )
    (net (code "43") (name "PWREN1") (class "Default")
      (node (ref "U1") (pin "4") (pinfunction "EN_4") (pintype "passive"))
    )
    (net (code "44") (name "PWREN2") (class "Default")
      (node (ref "U3") (pin "4") (pinfunction "EN_4") (pintype "passive"))
    )
    (net (code "45") (name "PWREN3") (class "Default")
      (node (ref "U2") (pin "4") (pinfunction "EN_4") (pintype "passive"))
    )
    (net (code "46") (name "PWREN4") (class "Default")
      (node (ref "U4") (pin "4") (pinfunction "EN_4") (pintype "passive"))
    )
    (net (code "47") (name "SHIELD") (class "Default")
      (node (ref "H1") (pin "1") (pintype "passive"))
      (node (ref "H2") (pin "1") (pintype "passive"))
      (node (ref "H3") (pin "1") (pintype "passive"))
      (node (ref "H4") (pin "1") (pintype "passive"))
      (node (ref "J1") (pin "G1") (pinfunction "G1_G1") (pintype "power_in"))
      (node (ref "J1") (pin "G2") (pinfunction "G2_G2") (pintype "power_in"))
      (node (ref "J2") (pin "G1") (pinfunction "G1_G1") (pintype "power_in"))
      (node (ref "J2") (pin "G2") (pinfunction "G2_G2") (pintype "power_in"))
      (node (ref "J3") (pin "G1") (pinfunction "G1_G1") (pintype "power_in"))
      (node (ref "J3") (pin "G2") (pinfunction "G2_G2") (pintype "power_in"))
      (node (ref "J4") (pin "G1") (pinfunction "G1_G1") (pintype "passive"))
      (node (ref "J4") (pin "G2") (pinfunction "G2_G2") (pintype "passive"))
      (node (ref "J4") (pin "G3") (pinfunction "G3_G3") (pintype "passive"))
      (node (ref "J4") (pin "G4") (pinfunction "G4_G4") (pintype "passive"))
      (node (ref "J4") (pin "G5") (pinfunction "G5_G5") (pintype "passive"))
      (node (ref "J4") (pin "G6") (pinfunction "G6_G6") (pintype "passive"))
      (node (ref "J5") (pin "G1") (pinfunction "G1_G1") (pintype "power_in"))
      (node (ref "J5") (pin "G2") (pinfunction "G2_G2") (pintype "power_in"))
    )
    (net (code "48") (name "SSRX0_N") (class "Default")
      (node (ref "D8") (pin "5") (pinfunction "K5_5") (pintype "passive"))
      (node (ref "D8") (pin "6") (pinfunction "K6_6") (pintype "passive"))
      (node (ref "J4") (pin "9") (pinfunction "SSRX+_9") (pintype "passive"))
    )
    (net (code "49") (name "SSRX0_P") (class "Default")
      (node (ref "D8") (pin "4") (pinfunction "K4_4") (pintype "passive"))
      (node (ref "D8") (pin "7") (pinfunction "K7_7") (pintype "passive"))
      (node (ref "J4") (pin "8") (pinfunction "SSRX-_8") (pintype "passive"))
    )
    (net (code "50") (name "SSRX1_N") (class "Default")
      (node (ref "D1") (pin "1") (pinfunction "K1_1") (pintype "passive"))
      (node (ref "D1") (pin "9") (pinfunction "K9_9") (pintype "passive"))
      (node (ref "J1") (pin "5") (pinfunction "SSRX-_5") (pintype "passive"))
    )
    (net (code "51") (name "SSRX1_P") (class "Default")
      (node (ref "D1") (pin "2") (pinfunction "K2_2") (pintype "passive"))
      (node (ref "D1") (pin "8") (pinfunction "K8_8") (pintype "passive"))
      (node (ref "J1") (pin "6") (pinfunction "SSRX+_6") (pintype "passive"))
    )
    (net (code "52") (name "SSRX2_N") (class "Default")
      (node (ref "D4") (pin "1") (pinfunction "K1_1") (pintype "passive"))
      (node (ref "D4") (pin "9") (pinfunction "K9_9") (pintype "passive"))
      (node (ref "J2") (pin "5") (pinfunction "SSRX-_5") (pintype "passive"))
    )
    (net (code "53") (name "SSRX2_P") (class "Default")
      (node (ref "D4") (pin "2") (pinfunction "K2_2") (pintype "passive"))
      (node (ref "D4") (pin "8") (pinfunction "K8_8") (pintype "passive"))
      (node (ref "J2") (pin "6") (pinfunction "SSRX+_6") (pintype "passive"))
    )
    (net (code "54") (name "SSRX3_N") (class "Default")
      (node (ref "D7") (pin "1") (pinfunction "K1_1") (pintype "passive"))
      (node (ref "D7") (pin "9") (pinfunction "K9_9") (pintype "passive"))
      (node (ref "J3") (pin "5") (pinfunction "SSRX-_5") (pintype "passive"))
    )
    (net (code "55") (name "SSRX3_P") (class "Default")
      (node (ref "D7") (pin "2") (pinfunction "K2_2") (pintype "passive"))
      (node (ref "D7") (pin "8") (pinfunction "K8_8") (pintype "passive"))
      (node (ref "J3") (pin "6") (pinfunction "SSRX+_6") (pintype "passive"))
    )
    (net (code "56") (name "SSRX4_N") (class "Default")
      (node (ref "D11") (pin "1") (pinfunction "K1_1") (pintype "passive"))
      (node (ref "D11") (pin "9") (pinfunction "K9_9") (pintype "passive"))
      (node (ref "J5") (pin "5") (pinfunction "SSRX-_5") (pintype "passive"))
    )
    (net (code "57") (name "SSRX4_P") (class "Default")
      (node (ref "D11") (pin "2") (pinfunction "K2_2") (pintype "passive"))
      (node (ref "D11") (pin "8") (pinfunction "K8_8") (pintype "passive"))
      (node (ref "J5") (pin "6") (pinfunction "SSRX+_6") (pintype "passive"))
    )
    (net (code "58") (name "SSTX0_N") (class "Default")
      (node (ref "C23") (pin "1") (pinfunction "1_1") (pintype "passive"))
    )
    (net (code "59") (name "SSTX0_P") (class "Default")
      (node (ref "C24") (pin "1") (pinfunction "1_1") (pintype "passive"))
    )
    (net (code "60") (name "SSTX1_N") (class "Default")
      (node (ref "C2") (pin "1") (pinfunction "1_1") (pintype "passive"))
    )
    (net (code "61") (name "SSTX1_P") (class "Default")
      (node (ref "C1") (pin "1") (pinfunction "1_1") (pintype "passive"))
    )
    (net (code "62") (name "SSTX2_N") (class "Default")
      (node (ref "C14") (pin "1") (pinfunction "1_1") (pintype "passive"))
    )
    (net (code "63") (name "SSTX2_P") (class "Default")
      (node (ref "C13") (pin "1") (pinfunction "1_1") (pintype "passive"))
    )
    (net (code "64") (name "SSTX3_N") (class "Default")
      (node (ref "C22") (pin "1") (pinfunction "1_1") (pintype "passive"))
    )
    (net (code "65") (name "SSTX3_P") (class "Default")
      (node (ref "C21") (pin "1") (pinfunction "1_1") (pintype "passive"))
    )
    (net (code "66") (name "SSTX4_N") (class "Default")
      (node (ref "C30") (pin "1") (pinfunction "1_1") (pintype "passive"))
    )
    (net (code "67") (name "SSTX4_P") (class "Default")
      (node (ref "C29") (pin "1") (pinfunction "1_1") (pintype "passive"))
    )
    (net (code "68") (name "USBDP_N") (class "Default")
      (node (ref "L4") (pin "3") (pinfunction "3_3") (pintype "passive"))
    )
    (net (code "69") (name "USBDP_P") (class "Default")
      (node (ref "L4") (pin "4") (pinfunction "4_4") (pintype "passive"))
    )
    (net (code "70") (name "USBHP1_N") (class "Default")
      (node (ref "L1") (pin "3") (pinfunction "3_3") (pintype "passive"))
    )
    (net (code "71") (name "USBHP1_P") (class "Default")
      (node (ref "L1") (pin "4") (pinfunction "4_4") (pintype "passive"))
    )
    (net (code "72") (name "USBHP2_N") (class "Default")
      (node (ref "L2") (pin "3") (pinfunction "3_3") (pintype "passive"))
    )
    (net (code "73") (name "USBHP2_P") (class "Default")
      (node (ref "L2") (pin "4") (pinfunction "4_4") (pintype "passive"))
    )
    (net (code "74") (name "USBHP3_N") (class "Default")
      (node (ref "L3") (pin "3") (pinfunction "3_3") (pintype "passive"))
    )
    (net (code "75") (name "USBHP3_P") (class "Default")
      (node (ref "L3") (pin "4") (pinfunction "4_4") (pintype "passive"))
    )
    (net (code "76") (name "USBHP4_N") (class "Default")
      (node (ref "L5") (pin "3") (pinfunction "3_3") (pintype "passive"))
    )
    (net (code "77") (name "USBHP4_P") (class "Default")
      (node (ref "L5") (pin "4") (pinfunction "4_4") (pintype "passive"))
    )
  )
)
